# Trace.net
KiCad netlist of a schematic drawn in Altium Designer
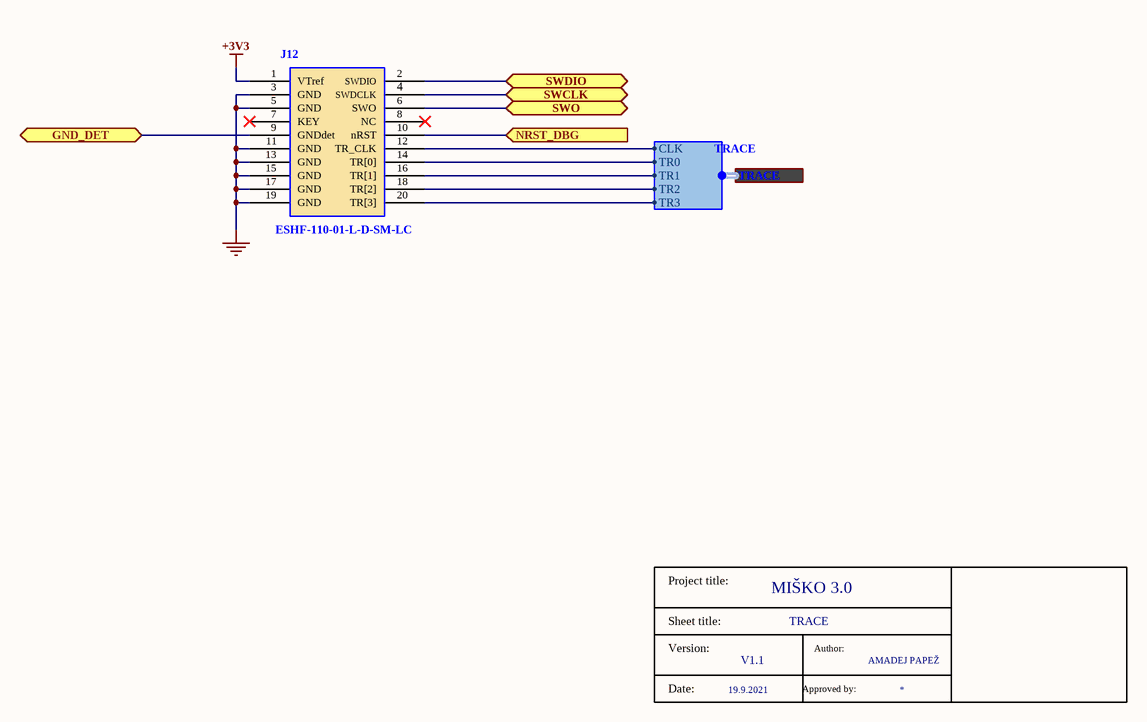
[diagram p0: Trace.SchDoc]

(export (version "E")
  (design (tool "Eeschema 10.0.6"))
  (components
    (comp (ref "J12")
      (value "ESHF-110-01-L-D-SM-LC")
      (footprint "ESHF-110-01-L-D-SM-LC")
      (description "Trace/JTAG/SW connector")
      (libsource (lib "MISKO3_V6") (part "ESHF-110-01-L-D-SM-LC"))
    )
    (comp (ref "T13") (value "~") (libsource (lib "MISKO3_V6") (part "Title block")))
  )
  (nets
    (net (code "2") (name "+3V3") (class "Default")
      (node (ref "J12") (pin "1") (pinfunction "VTref_1") (pintype "passive"))
    )
    (net (code "3") (name "/CLK") (class "Default")
      (node (ref "J12") (pin "12") (pinfunction "TR_CLK_12") (pintype "passive"))
    )
    (net (code "4") (name "/GND_DET") (class "Default")
      (node (ref "J12") (pin "9") (pinfunction "GNDdet_9") (pintype "passive"))
    )
    (net (code "5") (name "/NRST_DBG") (class "Default")
      (node (ref "J12") (pin "10") (pinfunction "nRST_10") (pintype "passive"))
    )
    (net (code "6") (name "/SWCLK") (class "Default")
      (node (ref "J12") (pin "4") (pinfunction "SWDCLK_4") (pintype "passive"))
    )
    (net (code "7") (name "/SWDIO") (class "Default")
      (node (ref "J12") (pin "2") (pinfunction "SWDIO_2") (pintype "passive"))
    )
    (net (code "8") (name "/SWO") (class "Default")
      (node (ref "J12") (pin "6") (pinfunction "SWO_6") (pintype "passive"))
    )
    (net (code "9") (name "/TR0") (class "Default")
      (node (ref "J12") (pin "14") (pinfunction "TR[0]_14") (pintype "passive"))
    )
    (net (code "10") (name "/TR1") (class "Default")
      (node (ref "J12") (pin "16") (pinfunction "TR[1]_16") (pintype "passive"))
    )
    (net (code "11") (name "/TR2") (class "Default")
      (node (ref "J12") (pin "18") (pinfunction "TR[2]_18") (pintype "passive"))
    )
    (net (code "12") (name "/TR3") (class "Default")
      (node (ref "J12") (pin "20") (pinfunction "TR[3]_20") (pintype "passive"))
    )
    (net (code "14") (name "GND") (class "Default")
      (node (ref "J12") (pin "11") (pinfunction "GND_11") (pintype "passive"))
      (node (ref "J12") (pin "13") (pinfunction "GND_13") (pintype "passive"))
      (node (ref "J12") (pin "15") (pinfunction "GND_15") (pintype "passive"))
      (node (ref "J12") (pin "17") (pinfunction "GND_17") (pintype "passive"))
      (node (ref "J12") (pin "19") (pinfunction "GND_19") (pintype "passive"))
      (node (ref "J12") (pin "3") (pinfunction "GND_3") (pintype "passive"))
      (node (ref "J12") (pin "5") (pinfunction "GND_5") (pintype "passive"))
    )
    (net (code "15") (name "unconnected-(J12-KEY-Pad7)") (class "Default")
      (node (ref "J12") (pin "7") (pinfunction "KEY_7") (pintype "passive+no_connect"))
    )
    (net (code "16") (name "unconnected-(J12-NC-Pad8)") (class "Default")
      (node (ref "J12") (pin "8") (pinfunction "NC_8") (pintype "passive+no_connect"))
    )
  )
)
